# PW-Stick.net
KiCad netlist of a schematic drawn in EAGLE
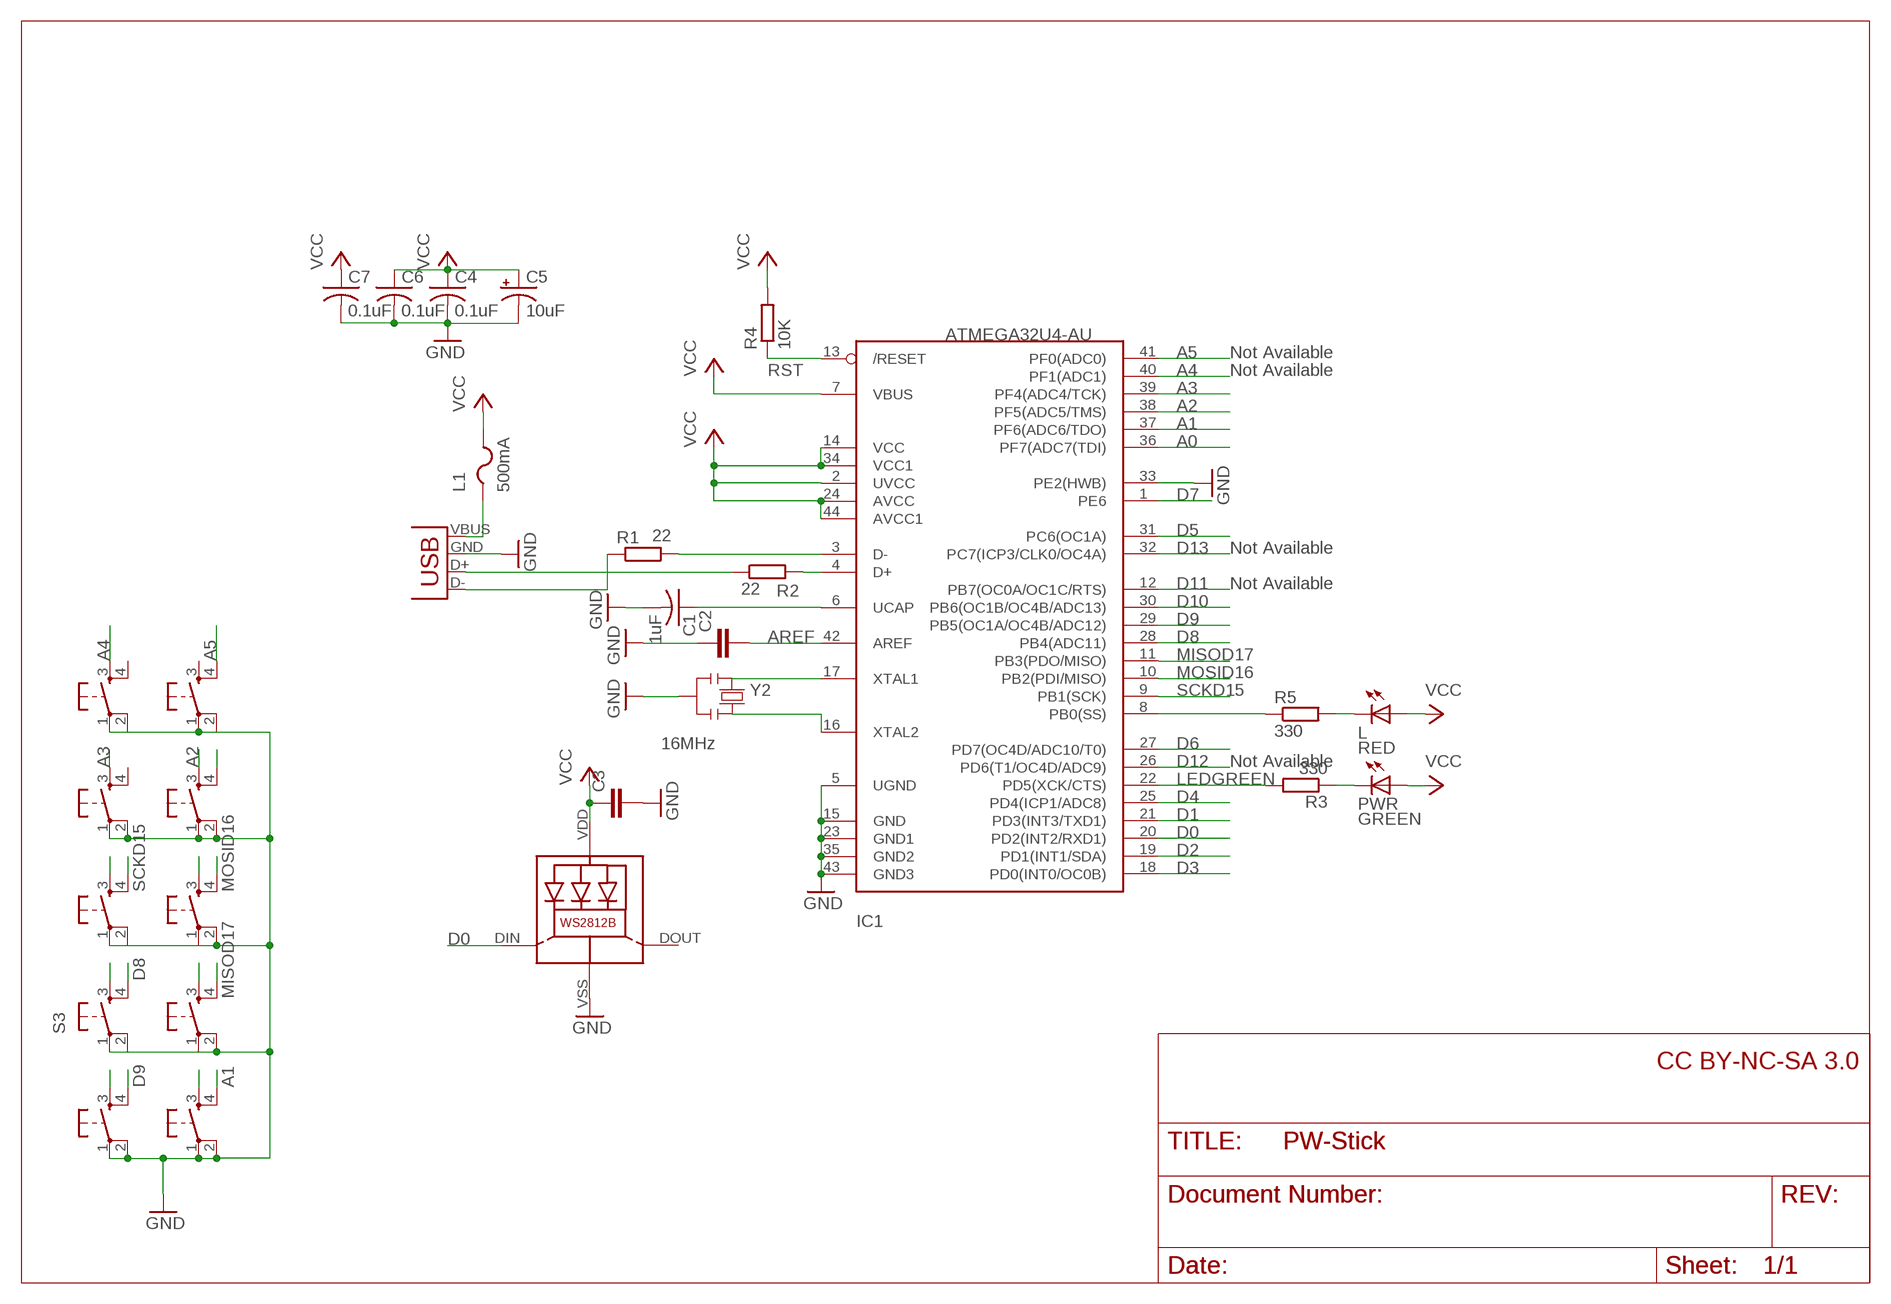
[diagram p0: schematic, sheet 1]

(export (version "E")
  (design (tool "Eeschema 10.0.6"))
  (components
    (comp (ref "C1")
      (value "1uF")
      (footprint "eagle-import:C0805K")
      (libsource (lib "eagle-import") (part "C-USC0805K"))
    )
    (comp (ref "C2")
      (value "C-EUC0805")
      (footprint "eagle-import:C0805")
      (libsource (lib "eagle-import") (part "C-EUC0805"))
    )
    (comp (ref "C3")
      (value "C-EUC0805")
      (footprint "eagle-import:C0805")
      (libsource (lib "eagle-import") (part "C-EUC0805"))
    )
    (comp (ref "C4")
      (value "0.1uF")
      (footprint "eagle-import:C0805K")
      (libsource (lib "eagle-import") (part "C-USC0805K"))
    )
    (comp (ref "C5")
      (value "10uF")
      (footprint "eagle-import:A_3216-18R")
      (libsource (lib "eagle-import") (part "CPOL-USA/3216-18R"))
    )
    (comp (ref "C6")
      (value "0.1uF")
      (footprint "eagle-import:C0805K")
      (libsource (lib "eagle-import") (part "C-USC0805K"))
    )
    (comp (ref "C7")
      (value "0.1uF")
      (footprint "eagle-import:C0805K")
      (libsource (lib "eagle-import") (part "C-USC0805K"))
    )
    (comp (ref "IC1")
      (value "ATMEGA32U4-AU")
      (footprint "eagle-import:TQFP44")
      (libsource (lib "eagle-import") (part "ATMEGA32U4-AU"))
    )
    (comp (ref "JP2")
      (value "USB-A-H")
      (footprint "eagle-import:USB-A-H")
      (libsource (lib "eagle-import") (part "USB-A-H"))
    )
    (comp (ref "L")
      (value "RED")
      (footprint "eagle-import:CHIPLED_0805")
      (libsource (lib "eagle-import") (part "LEDCHIPLED_0805"))
    )
    (comp (ref "L1")
      (value "500mA")
      (footprint "eagle-import:R1206")
      (libsource (lib "eagle-import") (part "PTCFUSE-1206"))
    )
    (comp (ref "LED1")
      (value "WS2812B")
      (footprint "eagle-import:WS2812B")
      (libsource (lib "eagle-import") (part "WS2812B"))
    )
    (comp (ref "PWR")
      (value "GREEN")
      (footprint "eagle-import:CHIPLED_0805")
      (libsource (lib "eagle-import") (part "LEDCHIPLED_0805"))
    )
    (comp (ref "R1")
      (value "22")
      (footprint "eagle-import:R0805")
      (libsource (lib "eagle-import") (part "R-EU_R0805"))
    )
    (comp (ref "R2")
      (value "22")
      (footprint "eagle-import:R0805")
      (libsource (lib "eagle-import") (part "R-EU_R0805"))
    )
    (comp (ref "R3")
      (value "330")
      (footprint "eagle-import:R0805")
      (libsource (lib "eagle-import") (part "R-EU_R0805"))
    )
    (comp (ref "R4")
      (value "10K")
      (footprint "eagle-import:R0805")
      (libsource (lib "eagle-import") (part "R-EU_R0805"))
    )
    (comp (ref "R5")
      (value "330")
      (footprint "eagle-import:R0805")
      (libsource (lib "eagle-import") (part "R-EU_R0805"))
    )
    (comp (ref "S1")
      (value "DTSM-6")
      (footprint "eagle-import:DTSM-6")
      (libsource (lib "eagle-import") (part "DTSM-6"))
    )
    (comp (ref "S2")
      (value "DTSM-6")
      (footprint "eagle-import:DTSM-6")
      (libsource (lib "eagle-import") (part "DTSM-6"))
    )
    (comp (ref "S3")
      (value "DTSM-6")
      (footprint "eagle-import:DTSM-6")
      (libsource (lib "eagle-import") (part "DTSM-6"))
    )
    (comp (ref "S4")
      (value "DTSM-6")
      (footprint "eagle-import:DTSM-6")
      (libsource (lib "eagle-import") (part "DTSM-6"))
    )
    (comp (ref "S5")
      (value "DTSM-6")
      (footprint "eagle-import:DTSM-6")
      (libsource (lib "eagle-import") (part "DTSM-6"))
    )
    (comp (ref "S6")
      (value "DTSM-6")
      (footprint "eagle-import:DTSM-6")
      (libsource (lib "eagle-import") (part "DTSM-6"))
    )
    (comp (ref "S7")
      (value "DTSM-6")
      (footprint "eagle-import:DTSM-6")
      (libsource (lib "eagle-import") (part "DTSM-6"))
    )
    (comp (ref "S8")
      (value "DTSM-6")
      (footprint "eagle-import:DTSM-6")
      (libsource (lib "eagle-import") (part "DTSM-6"))
    )
    (comp (ref "S9")
      (value "DTSM-6")
      (footprint "eagle-import:DTSM-6")
      (libsource (lib "eagle-import") (part "DTSM-6"))
    )
    (comp (ref "S10")
      (value "DTSM-6")
      (footprint "eagle-import:DTSM-6")
      (libsource (lib "eagle-import") (part "DTSM-6"))
    )
    (comp (ref "Y2")
      (value "16MHz")
      (footprint "eagle-import:RESONATOR")
      (libsource (lib "eagle-import") (part "RESONATORMU"))
    )
  )
  (nets
    (net (code "1") (name "/A0") (class "Default")
      (node (ref "IC1") (pin "36") (pinfunction "PF7(ADC7(TDI)_36") (pintype "bidirectional"))
    )
    (net (code "2") (name "/A1") (class "Default")
      (node (ref "IC1") (pin "37") (pinfunction "PF6(ADC6/TDO)_37") (pintype "bidirectional"))
      (node (ref "S2") (pin "4") (pinfunction "4_4") (pintype "passive"))
    )
    (net (code "3") (name "/A2") (class "Default")
      (node (ref "IC1") (pin "38") (pinfunction "PF5(ADC5/TMS)_38") (pintype "bidirectional"))
      (node (ref "S8") (pin "3") (pinfunction "3_3") (pintype "passive"))
    )
    (net (code "4") (name "/A3") (class "Default")
      (node (ref "IC1") (pin "39") (pinfunction "PF4(ADC4/TCK)_39") (pintype "bidirectional"))
      (node (ref "S7") (pin "3") (pinfunction "3_3") (pintype "passive"))
    )
    (net (code "5") (name "/A4") (class "Default")
      (node (ref "IC1") (pin "40") (pinfunction "PF1(ADC1)_40") (pintype "bidirectional"))
      (node (ref "S9") (pin "3") (pinfunction "3_3") (pintype "passive"))
    )
    (net (code "6") (name "/A5") (class "Default")
      (node (ref "IC1") (pin "41") (pinfunction "PF0(ADC0)_41") (pintype "bidirectional"))
      (node (ref "S10") (pin "4") (pinfunction "4_4") (pintype "passive"))
    )
    (net (code "7") (name "/AREF") (class "Default")
      (node (ref "C2") (pin "2") (pinfunction "2_2") (pintype "passive"))
      (node (ref "IC1") (pin "42") (pinfunction "AREF_42") (pintype "bidirectional"))
    )
    (net (code "8") (name "/D0") (class "Default")
      (node (ref "IC1") (pin "20") (pinfunction "PD2(INT2/RXD1)_20") (pintype "bidirectional"))
      (node (ref "LED1") (pin "DIN") (pinfunction "DI_DIN") (pintype "input"))
    )
    (net (code "9") (name "/D1") (class "Default")
      (node (ref "IC1") (pin "21") (pinfunction "PD3(INT3/TXD1)_21") (pintype "bidirectional"))
    )
    (net (code "10") (name "/D2") (class "Default")
      (node (ref "IC1") (pin "19") (pinfunction "PD1(INT1/SDA)_19") (pintype "bidirectional"))
    )
    (net (code "11") (name "/D3") (class "Default")
      (node (ref "IC1") (pin "18") (pinfunction "PD0(INT0/OC0B)_18") (pintype "bidirectional"))
    )
    (net (code "12") (name "/D4") (class "Default")
      (node (ref "IC1") (pin "25") (pinfunction "PD4(ICP1/ADC8)_25") (pintype "bidirectional"))
    )
    (net (code "13") (name "/D5") (class "Default")
      (node (ref "IC1") (pin "31") (pinfunction "PC6(OC1A)_31") (pintype "bidirectional"))
    )
    (net (code "14") (name "/D6") (class "Default")
      (node (ref "IC1") (pin "27") (pinfunction "PD7(OC4D/ADC10/T0)_27") (pintype "bidirectional"))
    )
    (net (code "15") (name "/D7") (class "Default")
      (node (ref "IC1") (pin "1") (pinfunction "PE6_1") (pintype "bidirectional"))
    )
    (net (code "16") (name "/D8") (class "Default")
      (node (ref "IC1") (pin "28") (pinfunction "PB4(ADC11)_28") (pintype "bidirectional"))
      (node (ref "S3") (pin "4") (pinfunction "4_4") (pintype "passive"))
    )
    (net (code "17") (name "/D9") (class "Default")
      (node (ref "IC1") (pin "29") (pinfunction "PB5(OC1A/OC4B/ADC12)_29") (pintype "bidirectional"))
      (node (ref "S1") (pin "4") (pinfunction "4_4") (pintype "passive"))
    )
    (net (code "18") (name "/D10") (class "Default")
      (node (ref "IC1") (pin "30") (pinfunction "PB6(OC1B/OC4B/ADC13)_30") (pintype "bidirectional"))
    )
    (net (code "19") (name "/D11") (class "Default")
      (node (ref "IC1") (pin "12") (pinfunction "PB7(OC0A/OC1C/RTS)_12") (pintype "bidirectional"))
    )
    (net (code "20") (name "/D12") (class "Default")
      (node (ref "IC1") (pin "26") (pinfunction "PD6(T1/OC4D/ADC9)_26") (pintype "bidirectional"))
    )
    (net (code "21") (name "/D13") (class "Default")
      (node (ref "IC1") (pin "32") (pinfunction "PC7(ICP3/CLK0/OC4A)_32") (pintype "bidirectional"))
    )
    (net (code "22") (name "/LEDGREEN") (class "Default")
      (node (ref "IC1") (pin "22") (pinfunction "PD5(XCK/CTS)_22") (pintype "bidirectional"))
      (node (ref "R3") (pin "2") (pinfunction "2_2") (pintype "passive"))
    )
    (net (code "23") (name "/MISOD17") (class "Default")
      (node (ref "IC1") (pin "11") (pinfunction "PB3(PDO/MISO)_11") (pintype "bidirectional"))
      (node (ref "S4") (pin "4") (pinfunction "4_4") (pintype "passive"))
    )
    (net (code "24") (name "/MOSID16") (class "Default")
      (node (ref "IC1") (pin "10") (pinfunction "PB2(PDI/MISO)_10") (pintype "bidirectional"))
      (node (ref "S6") (pin "3") (pinfunction "3_3") (pintype "passive"))
    )
    (net (code "25") (name "/RST") (class "Default")
      (node (ref "IC1") (pin "13") (pinfunction "/RESET_13") (pintype "bidirectional"))
      (node (ref "R4") (pin "1") (pinfunction "1_1") (pintype "passive"))
    )
    (net (code "26") (name "/SCKD15") (class "Default")
      (node (ref "IC1") (pin "9") (pinfunction "PB1(SCK)_9") (pintype "bidirectional"))
      (node (ref "S5") (pin "3") (pinfunction "3_3") (pintype "passive"))
    )
    (net (code "27") (name "GND") (class "Default")
      (node (ref "C1") (pin "2") (pinfunction "2_2") (pintype "passive"))
      (node (ref "C2") (pin "1") (pinfunction "1_1") (pintype "passive"))
      (node (ref "C3") (pin "2") (pinfunction "2_2") (pintype "passive"))
      (node (ref "C4") (pin "2") (pinfunction "2_2") (pintype "passive"))
      (node (ref "C5") (pin "-") (pinfunction "-_-") (pintype "passive"))
      (node (ref "C6") (pin "2") (pinfunction "2_2") (pintype "passive"))
      (node (ref "C7") (pin "2") (pinfunction "2_2") (pintype "passive"))
      (node (ref "IC1") (pin "15") (pinfunction "GND_15") (pintype "bidirectional"))
      (node (ref "IC1") (pin "23") (pinfunction "GND1_23") (pintype "bidirectional"))
      (node (ref "IC1") (pin "33") (pinfunction "PE2(HWB)_33") (pintype "bidirectional"))
      (node (ref "IC1") (pin "35") (pinfunction "GND2_35") (pintype "bidirectional"))
      (node (ref "IC1") (pin "43") (pinfunction "GND3_43") (pintype "bidirectional"))
      (node (ref "IC1") (pin "5") (pinfunction "UGND_5") (pintype "bidirectional"))
      (node (ref "JP2") (pin "GND") (pinfunction "VBUS_GND") (pintype "bidirectional"))
      (node (ref "LED1") (pin "VSS") (pinfunction "GND_VSS") (pintype "power_in"))
      (node (ref "S1") (pin "1") (pinfunction "1_1") (pintype "passive"))
      (node (ref "S1") (pin "2") (pinfunction "2_2") (pintype "passive"))
      (node (ref "S10") (pin "1") (pinfunction "1_1") (pintype "passive"))
      (node (ref "S2") (pin "1") (pinfunction "1_1") (pintype "passive"))
      (node (ref "S2") (pin "2") (pinfunction "2_2") (pintype "passive"))
      (node (ref "S3") (pin "1") (pinfunction "1_1") (pintype "passive"))
      (node (ref "S4") (pin "2") (pinfunction "2_2") (pintype "passive"))
      (node (ref "S5") (pin "1") (pinfunction "1_1") (pintype "passive"))
      (node (ref "S6") (pin "2") (pinfunction "2_2") (pintype "passive"))
      (node (ref "S7") (pin "1") (pinfunction "1_1") (pintype "passive"))
      (node (ref "S7") (pin "2") (pinfunction "2_2") (pintype "passive"))
      (node (ref "S8") (pin "1") (pinfunction "1_1") (pintype "passive"))
      (node (ref "S8") (pin "2") (pinfunction "2_2") (pintype "passive"))
      (node (ref "S9") (pin "1") (pinfunction "1_1") (pintype "passive"))
      (node (ref "Y2") (pin "2") (pinfunction "2_2") (pintype "passive"))
    )
    (net (code "28") (name "Net-(IC1-D+)") (class "Default")
      (node (ref "IC1") (pin "4") (pinfunction "D+_4") (pintype "bidirectional"))
      (node (ref "R2") (pin "2") (pinfunction "2_2") (pintype "passive"))
    )
    (net (code "29") (name "Net-(IC1-D-)") (class "Default")
      (node (ref "IC1") (pin "3") (pinfunction "D-_3") (pintype "bidirectional"))
      (node (ref "R1") (pin "2") (pinfunction "2_2") (pintype "passive"))
    )
    (net (code "30") (name "Net-(IC1-PB0(SS))") (class "Default")
      (node (ref "IC1") (pin "8") (pinfunction "PB0(SS)_8") (pintype "bidirectional"))
      (node (ref "R5") (pin "1") (pinfunction "1_1") (pintype "passive"))
    )
    (net (code "31") (name "Net-(IC1-UCAP)") (class "Default")
      (node (ref "C1") (pin "1") (pinfunction "1_1") (pintype "passive"))
      (node (ref "IC1") (pin "6") (pinfunction "UCAP_6") (pintype "bidirectional"))
    )
    (net (code "32") (name "Net-(IC1-XTAL1)") (class "Default")
      (node (ref "IC1") (pin "17") (pinfunction "XTAL1_17") (pintype "bidirectional"))
      (node (ref "Y2") (pin "1") (pinfunction "1_1") (pintype "passive"))
    )
    (net (code "33") (name "Net-(IC1-XTAL2)") (class "Default")
      (node (ref "IC1") (pin "16") (pinfunction "XTAL2_16") (pintype "bidirectional"))
      (node (ref "Y2") (pin "3") (pinfunction "3_3") (pintype "passive"))
    )
    (net (code "34") (name "Net-(JP2-D+)") (class "Default")
      (node (ref "JP2") (pin "D-") (pinfunction "D+_D-") (pintype "bidirectional"))
      (node (ref "R1") (pin "1") (pinfunction "1_1") (pintype "passive"))
    )
    (net (code "35") (name "Net-(JP2-D-)") (class "Default")
      (node (ref "JP2") (pin "D+") (pinfunction "D-_D+") (pintype "bidirectional"))
      (node (ref "R2") (pin "1") (pinfunction "1_1") (pintype "passive"))
    )
    (net (code "36") (name "Net-(JP2-GND)") (class "Default")
      (node (ref "JP2") (pin "VBUS") (pinfunction "GND_VBUS") (pintype "bidirectional"))
      (node (ref "L1") (pin "1") (pinfunction "1_1") (pintype "passive"))
    )
    (net (code "37") (name "Net-(L-PadC)") (class "Default")
      (node (ref "L") (pin "C") (pinfunction "C_C") (pintype "passive"))
      (node (ref "R5") (pin "2") (pinfunction "2_2") (pintype "passive"))
    )
    (net (code "38") (name "Net-(PWR-PadC)") (class "Default")
      (node (ref "PWR") (pin "C") (pinfunction "C_C") (pintype "passive"))
      (node (ref "R3") (pin "1") (pinfunction "1_1") (pintype "passive"))
    )
    (net (code "39") (name "VCC") (class "Default")
      (node (ref "C3") (pin "1") (pinfunction "1_1") (pintype "passive"))
      (node (ref "C4") (pin "1") (pinfunction "1_1") (pintype "passive"))
      (node (ref "C5") (pin "+") (pinfunction "+_+") (pintype "passive"))
      (node (ref "C6") (pin "1") (pinfunction "1_1") (pintype "passive"))
      (node (ref "C7") (pin "1") (pinfunction "1_1") (pintype "passive"))
      (node (ref "IC1") (pin "14") (pinfunction "VCC_14") (pintype "bidirectional"))
      (node (ref "IC1") (pin "2") (pinfunction "UVCC_2") (pintype "bidirectional"))
      (node (ref "IC1") (pin "24") (pinfunction "AVCC_24") (pintype "bidirectional"))
      (node (ref "IC1") (pin "34") (pinfunction "VCC1_34") (pintype "bidirectional"))
      (node (ref "IC1") (pin "44") (pinfunction "AVCC1_44") (pintype "bidirectional"))
      (node (ref "IC1") (pin "7") (pinfunction "VBUS_7") (pintype "bidirectional"))
      (node (ref "L") (pin "A") (pinfunction "A_A") (pintype "passive"))
      (node (ref "L1") (pin "2") (pinfunction "2_2") (pintype "passive"))
      (node (ref "LED1") (pin "VDD") (pinfunction "VDD_VDD") (pintype "power_in"))
      (node (ref "PWR") (pin "A") (pinfunction "A_A") (pintype "passive"))
      (node (ref "R4") (pin "2") (pinfunction "2_2") (pintype "passive"))
    )
    (net (code "40") (name "unconnected-(LED1-DO-PadDOUT)") (class "Default")
      (node (ref "LED1") (pin "DOUT") (pinfunction "DO_DOUT") (pintype "output"))
    )
    (net (code "41") (name "unconnected-(S1-Pad3)") (class "Default")
      (node (ref "S1") (pin "3") (pinfunction "3_3") (pintype "passive"))
    )
    (net (code "42") (name "unconnected-(S2-Pad3)") (class "Default")
      (node (ref "S2") (pin "3") (pinfunction "3_3") (pintype "passive"))
    )
    (net (code "43") (name "unconnected-(S3-Pad2)") (class "Default")
      (node (ref "S3") (pin "2") (pinfunction "2_2") (pintype "passive"))
    )
    (net (code "44") (name "unconnected-(S3-Pad3)") (class "Default")
      (node (ref "S3") (pin "3") (pinfunction "3_3") (pintype "passive"))
    )
    (net (code "45") (name "unconnected-(S4-Pad1)") (class "Default")
      (node (ref "S4") (pin "1") (pinfunction "1_1") (pintype "passive"))
    )
    (net (code "46") (name "unconnected-(S4-Pad3)") (class "Default")
      (node (ref "S4") (pin "3") (pinfunction "3_3") (pintype "passive"))
    )
    (net (code "47") (name "unconnected-(S5-Pad2)") (class "Default")
      (node (ref "S5") (pin "2") (pinfunction "2_2") (pintype "passive"))
    )
    (net (code "48") (name "unconnected-(S5-Pad4)") (class "Default")
      (node (ref "S5") (pin "4") (pinfunction "4_4") (pintype "passive"))
    )
    (net (code "49") (name "unconnected-(S6-Pad1)") (class "Default")
      (node (ref "S6") (pin "1") (pinfunction "1_1") (pintype "passive"))
    )
    (net (code "50") (name "unconnected-(S6-Pad4)") (class "Default")
      (node (ref "S6") (pin "4") (pinfunction "4_4") (pintype "passive"))
    )
    (net (code "51") (name "unconnected-(S7-Pad4)") (class "Default")
      (node (ref "S7") (pin "4") (pinfunction "4_4") (pintype "passive"))
    )
    (net (code "52") (name "unconnected-(S8-Pad4)") (class "Default")
      (node (ref "S8") (pin "4") (pinfunction "4_4") (pintype "passive"))
    )
    (net (code "53") (name "unconnected-(S9-Pad2)") (class "Default")
      (node (ref "S9") (pin "2") (pinfunction "2_2") (pintype "passive"))
    )
    (net (code "54") (name "unconnected-(S9-Pad4)") (class "Default")
      (node (ref "S9") (pin "4") (pinfunction "4_4") (pintype "passive"))
    )
    (net (code "55") (name "unconnected-(S10-Pad2)") (class "Default")
      (node (ref "S10") (pin "2") (pinfunction "2_2") (pintype "passive"))
    )
    (net (code "56") (name "unconnected-(S10-Pad3)") (class "Default")
      (node (ref "S10") (pin "3") (pinfunction "3_3") (pintype "passive"))
    )
  )
)
